# atsamdg21_rtc.net
KiCad netlist of a schematic drawn in EAGLE
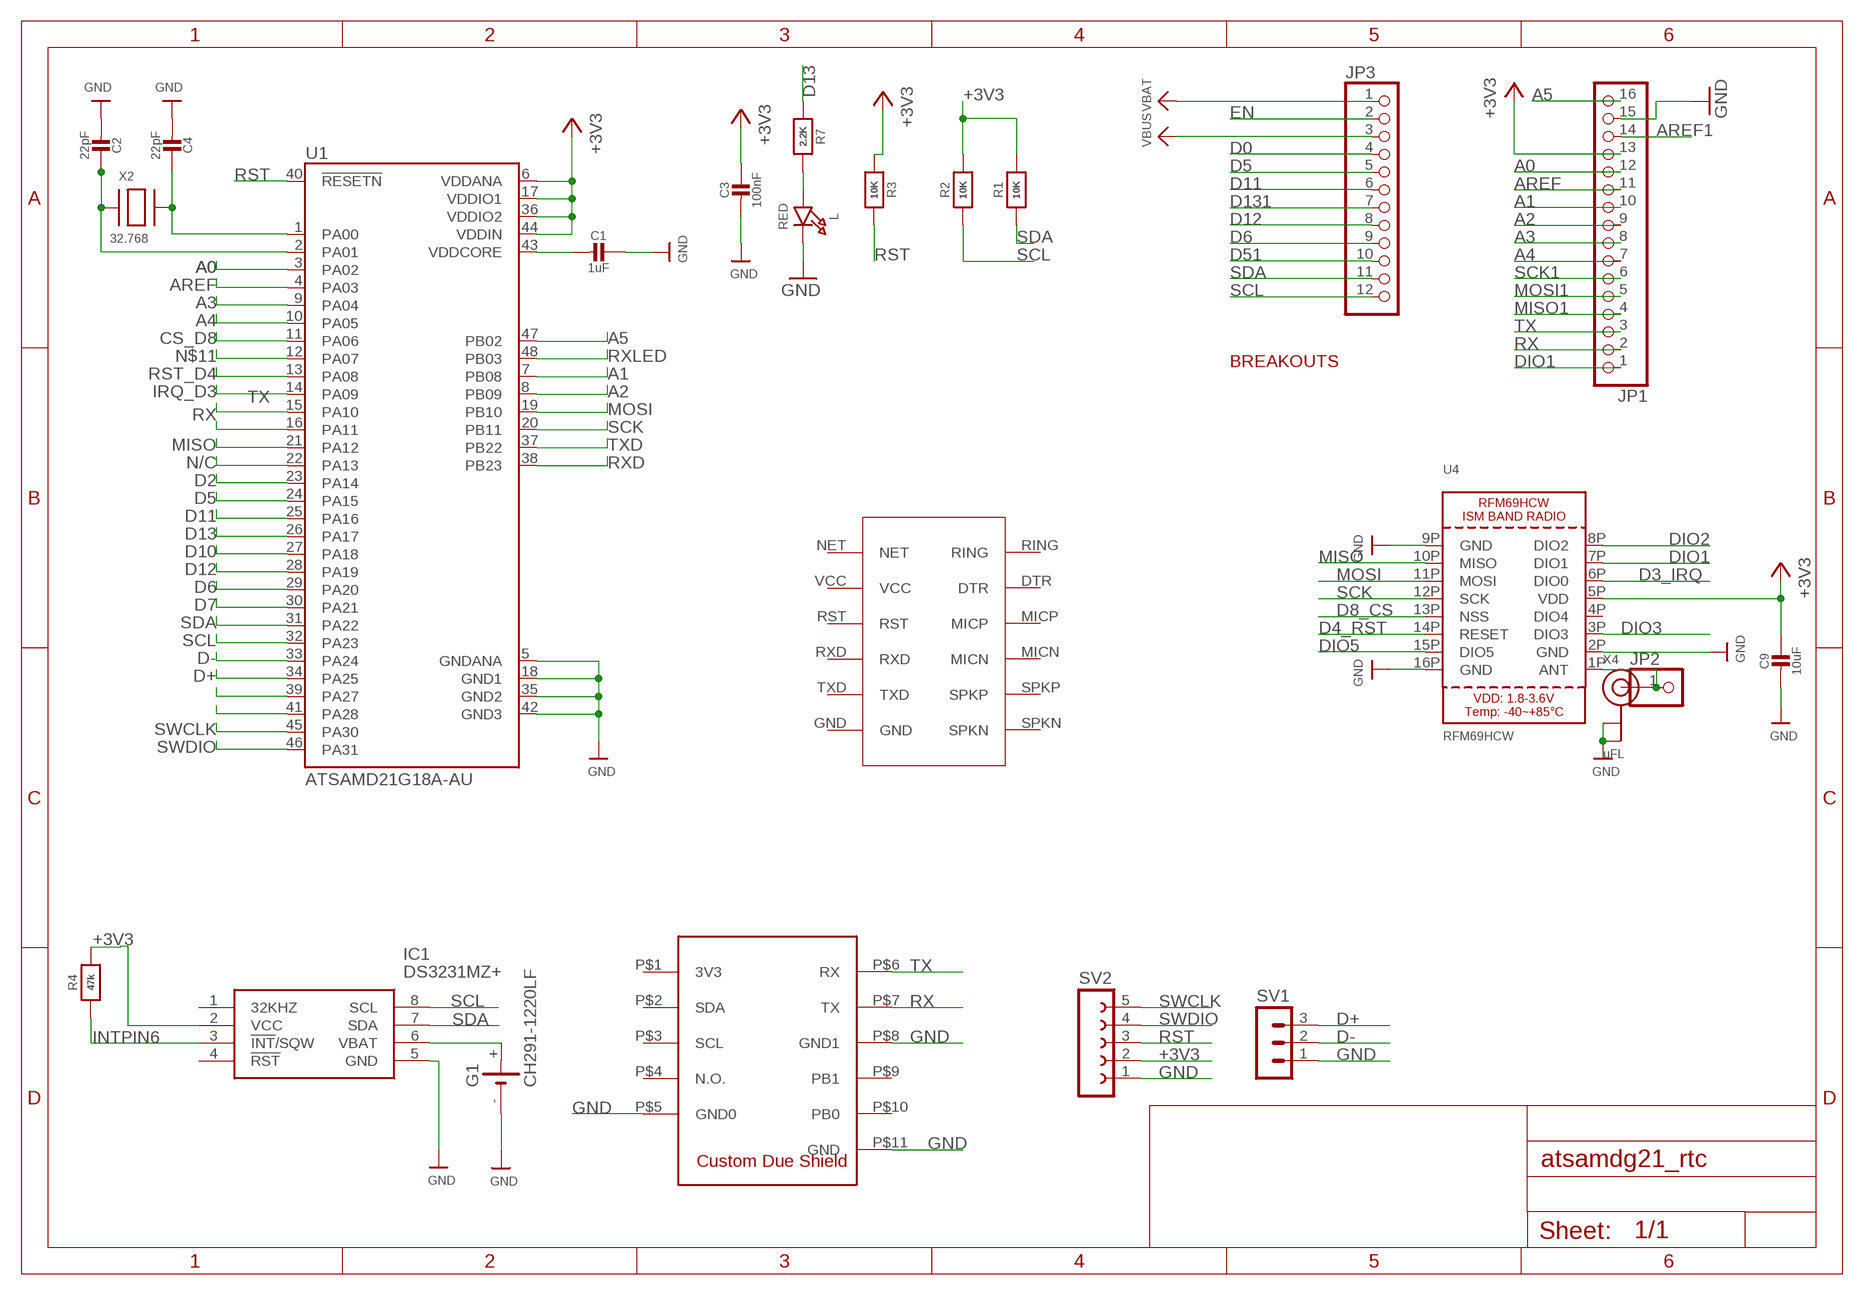
[diagram p0: schematic, sheet 1]

(export (version "E")
  (design (tool "Eeschema 10.0.6"))
  (components
    (comp (ref "C1")
      (value "1uF")
      (footprint "eagle-import:0603-NO")
      (libsource (lib "eagle-import") (part "CAP_CERAMIC0603_NO"))
    )
    (comp (ref "C2")
      (value "22pF")
      (footprint "eagle-import:0603-NO")
      (libsource (lib "eagle-import") (part "CAP_CERAMIC0603_NO"))
    )
    (comp (ref "C3")
      (value "100nF")
      (footprint "eagle-import:0603-NO")
      (libsource (lib "eagle-import") (part "CAP_CERAMIC0603_NO"))
    )
    (comp (ref "C4")
      (value "22pF")
      (footprint "eagle-import:0603-NO")
      (libsource (lib "eagle-import") (part "CAP_CERAMIC0603_NO"))
    )
    (comp (ref "C9")
      (value "10uF")
      (footprint "eagle-import:0805-NO")
      (libsource (lib "eagle-import") (part "CAP_CERAMIC0805-NOOUTLINE"))
    )
    (comp (ref "G1")
      (value "CH291-1220LF")
      (footprint "eagle-import:CH291-1220LF")
      (libsource (lib "eagle-import") (part "CH291-1220LF"))
    )
    (comp (ref "IC1")
      (value "DS3231MZ+")
      (footprint "eagle-import:SOIC127P600X175-8N")
      (fields (field (name "RS_PART_NUMBER") "1897249"))
      (libsource (lib "eagle-import") (part "DS3231MZ+"))
    )
    (comp (ref "JP1")
      (value "HEADER-1X16ROUND")
      (footprint "eagle-import:1X16_ROUND")
      (libsource (lib "eagle-import") (part "HEADER-1X16ROUND"))
    )
    (comp (ref "JP2")
      (value "HEADER-1X1ROUND")
      (footprint "eagle-import:1X01_ROUND")
      (libsource (lib "eagle-import") (part "HEADER-1X1ROUND"))
    )
    (comp (ref "JP3")
      (value "HEADER-1X12")
      (footprint "eagle-import:1X12_ROUND")
      (libsource (lib "eagle-import") (part "HEADER-1X12"))
    )
    (comp (ref "L")
      (value "RED")
      (footprint "eagle-import:CHIPLED_0805_NOOUTLINE")
      (libsource (lib "eagle-import") (part "LED0805_NOOUTLINE"))
    )
    (comp (ref "R1")
      (value "10K")
      (footprint "eagle-import:0603-NO")
      (libsource (lib "eagle-import") (part "RESISTOR_0603_NOOUT"))
    )
    (comp (ref "R2")
      (value "10K")
      (footprint "eagle-import:0603-NO")
      (libsource (lib "eagle-import") (part "RESISTOR_0603_NOOUT"))
    )
    (comp (ref "R3")
      (value "10K")
      (footprint "eagle-import:0603-NO")
      (libsource (lib "eagle-import") (part "RESISTOR_0603_NOOUT"))
    )
    (comp (ref "R4")
      (value "47k")
      (footprint "eagle-import:0603-NO")
      (libsource (lib "eagle-import") (part "RESISTOR_0603_NOOUT"))
    )
    (comp (ref "R7")
      (value "2.2K")
      (footprint "eagle-import:0603-NO")
      (libsource (lib "eagle-import") (part "RESISTOR_0603_NOOUT"))
    )
    (comp (ref "SV1")
      (value "MA03-1")
      (footprint "eagle-import:MA03-1")
      (libsource (lib "eagle-import") (part "MA03-1"))
    )
    (comp (ref "SV2")
      (value "FE05-1")
      (footprint "eagle-import:FE05-1")
      (libsource (lib "eagle-import") (part "FE05-1"))
    )
    (comp (ref "U$7")
      (value "SIM800L_MODULE")
      (footprint "eagle-import:SIM800L")
      (libsource (lib "eagle-import") (part "SIM800L_MODULE"))
    )
    (comp (ref "U$9")
      (value "DUE_PADS")
      (footprint "eagle-import:DUESHIELD")
      (libsource (lib "eagle-import") (part "DUE_PADS"))
    )
    (comp (ref "U1")
      (value "ATSAMD21G18A-AU")
      (footprint "eagle-import:QFP50P900X900X120-48N")
      (fields (field (name "MF") "Microchip"))
      (libsource (lib "eagle-import") (part "ATSAMD21G18A-AU"))
    )
    (comp (ref "U4")
      (value "RFM69HCW")
      (footprint "eagle-import:RFMHCW_SMT")
      (libsource (lib "eagle-import") (part "RFM69HCW_SMT"))
    )
    (comp (ref "X2")
      (value "32.768")
      (footprint "eagle-import:XTAL3215")
      (libsource (lib "eagle-import") (part "XTAL-3.2X1.5"))
    )
    (comp (ref "X4")
      (value "uFL")
      (footprint "eagle-import:U.FL")
      (libsource (lib "eagle-import") (part "ANTENNA_U.FL"))
    )
  )
  (nets
    (net (code "1") (name "+3V3") (class "Default")
      (node (ref "C3") (pin "1") (pinfunction "1_1") (pintype "passive"))
      (node (ref "C9") (pin "1") (pinfunction "1_1") (pintype "passive"))
      (node (ref "IC1") (pin "2") (pinfunction "VCC_2") (pintype "power_in"))
      (node (ref "JP1") (pin "13") (pinfunction "13_13") (pintype "passive"))
      (node (ref "R1") (pin "2") (pinfunction "2_2") (pintype "passive"))
      (node (ref "R2") (pin "2") (pinfunction "2_2") (pintype "passive"))
      (node (ref "R3") (pin "1") (pinfunction "1_1") (pintype "passive"))
      (node (ref "R4") (pin "2") (pinfunction "2_2") (pintype "passive"))
      (node (ref "SV2") (pin "2") (pinfunction "2_2") (pintype "passive"))
      (node (ref "U1") (pin "17") (pinfunction "VDDIO1_17") (pintype "power_in"))
      (node (ref "U1") (pin "36") (pinfunction "VDDIO2_36") (pintype "power_in"))
      (node (ref "U1") (pin "44") (pinfunction "VDDIN_44") (pintype "power_in"))
      (node (ref "U1") (pin "6") (pinfunction "VDDANA_6") (pintype "power_in"))
      (node (ref "U4") (pin "5P") (pinfunction "VDD_5P") (pintype "power_in"))
    )
    (net (code "2") (name "/A0") (class "Default")
      (node (ref "JP1") (pin "12") (pinfunction "12_12") (pintype "passive"))
      (node (ref "U1") (pin "3") (pinfunction "PA02_3") (pintype "bidirectional"))
    )
    (net (code "3") (name "/A1") (class "Default")
      (node (ref "JP1") (pin "10") (pinfunction "10_10") (pintype "passive"))
      (node (ref "U1") (pin "7") (pinfunction "PB08_7") (pintype "bidirectional"))
    )
    (net (code "4") (name "/A2") (class "Default")
      (node (ref "JP1") (pin "9") (pinfunction "9_9") (pintype "passive"))
      (node (ref "U1") (pin "8") (pinfunction "PB09_8") (pintype "bidirectional"))
    )
    (net (code "5") (name "/A3") (class "Default")
      (node (ref "JP1") (pin "8") (pinfunction "8_8") (pintype "passive"))
      (node (ref "U1") (pin "9") (pinfunction "PA04_9") (pintype "bidirectional"))
    )
    (net (code "6") (name "/A4") (class "Default")
      (node (ref "JP1") (pin "7") (pinfunction "7_7") (pintype "passive"))
      (node (ref "U1") (pin "10") (pinfunction "PA05_10") (pintype "bidirectional"))
    )
    (net (code "7") (name "/A5") (class "Default")
      (node (ref "JP1") (pin "16") (pinfunction "16_16") (pintype "passive"))
      (node (ref "U1") (pin "47") (pinfunction "PB02_47") (pintype "bidirectional"))
    )
    (net (code "8") (name "/AREF") (class "Default")
      (node (ref "JP1") (pin "11") (pinfunction "11_11") (pintype "passive"))
      (node (ref "U1") (pin "4") (pinfunction "PA03_4") (pintype "bidirectional"))
    )
    (net (code "9") (name "/AREF1") (class "Default")
      (node (ref "JP1") (pin "14") (pinfunction "14_14") (pintype "passive"))
    )
    (net (code "10") (name "/CS_D8") (class "Default")
      (node (ref "U1") (pin "11") (pinfunction "PA06_11") (pintype "bidirectional"))
    )
    (net (code "11") (name "/D+") (class "Default")
      (node (ref "SV1") (pin "3") (pinfunction "3_3") (pintype "passive"))
      (node (ref "U1") (pin "34") (pinfunction "PA25_34") (pintype "bidirectional"))
    )
    (net (code "12") (name "/D-") (class "Default")
      (node (ref "SV1") (pin "2") (pinfunction "2_2") (pintype "passive"))
      (node (ref "U1") (pin "33") (pinfunction "PA24_33") (pintype "bidirectional"))
    )
    (net (code "13") (name "/D0") (class "Default")
      (node (ref "JP3") (pin "4") (pinfunction "4_4") (pintype "passive"))
    )
    (net (code "14") (name "/D2") (class "Default")
      (node (ref "U1") (pin "23") (pinfunction "PA14_23") (pintype "bidirectional"))
    )
    (net (code "15") (name "/D3_IRQ") (class "Default")
      (node (ref "U4") (pin "6P") (pinfunction "DIO0_6P") (pintype "bidirectional"))
    )
    (net (code "16") (name "/D4_RST") (class "Default")
      (node (ref "U4") (pin "14P") (pinfunction "RESET_14P") (pintype "input"))
    )
    (net (code "17") (name "/D5") (class "Default")
      (node (ref "JP3") (pin "5") (pinfunction "5_5") (pintype "passive"))
      (node (ref "U1") (pin "24") (pinfunction "PA15_24") (pintype "bidirectional"))
    )
    (net (code "18") (name "/D6") (class "Default")
      (node (ref "JP3") (pin "9") (pinfunction "9_9") (pintype "passive"))
      (node (ref "U1") (pin "29") (pinfunction "PA20_29") (pintype "bidirectional"))
    )
    (net (code "19") (name "/D7") (class "Default")
      (node (ref "U1") (pin "30") (pinfunction "PA21_30") (pintype "bidirectional"))
    )
    (net (code "20") (name "/D8_CS") (class "Default")
      (node (ref "U4") (pin "13P") (pinfunction "NSS_13P") (pintype "input"))
    )
    (net (code "21") (name "/D10") (class "Default")
      (node (ref "U1") (pin "27") (pinfunction "PA18_27") (pintype "bidirectional"))
    )
    (net (code "22") (name "/D11") (class "Default")
      (node (ref "JP3") (pin "6") (pinfunction "6_6") (pintype "passive"))
      (node (ref "U1") (pin "25") (pinfunction "PA16_25") (pintype "bidirectional"))
    )
    (net (code "23") (name "/D12") (class "Default")
      (node (ref "JP3") (pin "8") (pinfunction "8_8") (pintype "passive"))
      (node (ref "U1") (pin "28") (pinfunction "PA19_28") (pintype "bidirectional"))
    )
    (net (code "24") (name "/D13") (class "Default")
      (node (ref "R7") (pin "1") (pinfunction "1_1") (pintype "passive"))
      (node (ref "U1") (pin "26") (pinfunction "PA17_26") (pintype "bidirectional"))
    )
    (net (code "25") (name "/D51") (class "Default")
      (node (ref "JP3") (pin "10") (pinfunction "10_10") (pintype "passive"))
    )
    (net (code "26") (name "/D131") (class "Default")
      (node (ref "JP3") (pin "7") (pinfunction "7_7") (pintype "passive"))
    )
    (net (code "27") (name "/DIO1") (class "Default")
      (node (ref "JP1") (pin "1") (pinfunction "1_1") (pintype "passive"))
      (node (ref "U4") (pin "7P") (pinfunction "DIO1_7P") (pintype "bidirectional"))
    )
    (net (code "28") (name "/DIO2") (class "Default")
      (node (ref "U4") (pin "8P") (pinfunction "DIO2_8P") (pintype "bidirectional"))
    )
    (net (code "29") (name "/DIO3") (class "Default")
      (node (ref "U4") (pin "3P") (pinfunction "DIO3_3P") (pintype "bidirectional"))
    )
    (net (code "30") (name "/DIO5") (class "Default")
      (node (ref "U4") (pin "15P") (pinfunction "DIO5_15P") (pintype "bidirectional"))
    )
    (net (code "31") (name "/EN") (class "Default")
      (node (ref "JP3") (pin "2") (pinfunction "2_2") (pintype "passive"))
    )
    (net (code "32") (name "/INTPIN6") (class "Default")
      (node (ref "IC1") (pin "3") (pinfunction "~{INT}/SQW_3") (pintype "input"))
      (node (ref "R4") (pin "1") (pinfunction "1_1") (pintype "passive"))
    )
    (net (code "33") (name "/IRQ_D3") (class "Default")
      (node (ref "U1") (pin "14") (pinfunction "PA09_14") (pintype "bidirectional"))
    )
    (net (code "34") (name "/MISO") (class "Default")
      (node (ref "U1") (pin "21") (pinfunction "PA12_21") (pintype "bidirectional"))
      (node (ref "U4") (pin "10P") (pinfunction "MISO_10P") (pintype "output"))
    )
    (net (code "35") (name "/MISO1") (class "Default")
      (node (ref "JP1") (pin "4") (pinfunction "4_4") (pintype "passive"))
    )
    (net (code "36") (name "/MOSI") (class "Default")
      (node (ref "U1") (pin "19") (pinfunction "PB10_19") (pintype "bidirectional"))
      (node (ref "U4") (pin "11P") (pinfunction "MOSI_11P") (pintype "input"))
    )
    (net (code "37") (name "/MOSI1") (class "Default")
      (node (ref "JP1") (pin "5") (pinfunction "5_5") (pintype "passive"))
    )
    (net (code "38") (name "/N$11") (class "Default")
      (node (ref "U1") (pin "12") (pinfunction "PA07_12") (pintype "bidirectional"))
    )
    (net (code "39") (name "/N{slash}C") (class "Default")
      (node (ref "U1") (pin "22") (pinfunction "PA13_22") (pintype "bidirectional"))
    )
    (net (code "40") (name "/RST") (class "Default")
      (node (ref "R3") (pin "2") (pinfunction "2_2") (pintype "passive"))
      (node (ref "SV2") (pin "3") (pinfunction "3_3") (pintype "passive"))
      (node (ref "U1") (pin "40") (pinfunction "~{RESETN}_40") (pintype "input"))
    )
    (net (code "41") (name "/RST_D4") (class "Default")
      (node (ref "U1") (pin "13") (pinfunction "PA08_13") (pintype "bidirectional"))
    )
    (net (code "42") (name "/RX") (class "Default")
      (node (ref "JP1") (pin "2") (pinfunction "2_2") (pintype "passive"))
      (node (ref "U$9") (pin "P$7") (pinfunction "TX_P$7") (pintype "bidirectional"))
      (node (ref "U1") (pin "16") (pinfunction "PA11_16") (pintype "bidirectional"))
    )
    (net (code "43") (name "/RXD") (class "Default")
      (node (ref "U1") (pin "38") (pinfunction "PB23_38") (pintype "bidirectional"))
    )
    (net (code "44") (name "/RXLED") (class "Default")
      (node (ref "U1") (pin "48") (pinfunction "PB03_48") (pintype "bidirectional"))
    )
    (net (code "45") (name "/SCK") (class "Default")
      (node (ref "U1") (pin "20") (pinfunction "PB11_20") (pintype "bidirectional"))
      (node (ref "U4") (pin "12P") (pinfunction "SCK_12P") (pintype "input"))
    )
    (net (code "46") (name "/SCK1") (class "Default")
      (node (ref "JP1") (pin "6") (pinfunction "6_6") (pintype "passive"))
    )
    (net (code "47") (name "/SCL") (class "Default")
      (node (ref "IC1") (pin "8") (pinfunction "SCL_8") (pintype "bidirectional"))
      (node (ref "JP3") (pin "12") (pinfunction "12_12") (pintype "passive"))
      (node (ref "R2") (pin "1") (pinfunction "1_1") (pintype "passive"))
      (node (ref "U1") (pin "32") (pinfunction "PA23_32") (pintype "bidirectional"))
    )
    (net (code "48") (name "/SDA") (class "Default")
      (node (ref "IC1") (pin "7") (pinfunction "SDA_7") (pintype "bidirectional"))
      (node (ref "JP3") (pin "11") (pinfunction "11_11") (pintype "passive"))
      (node (ref "R1") (pin "1") (pinfunction "1_1") (pintype "passive"))
      (node (ref "U1") (pin "31") (pinfunction "PA22_31") (pintype "bidirectional"))
    )
    (net (code "49") (name "/SWCLK") (class "Default")
      (node (ref "SV2") (pin "5") (pinfunction "5_5") (pintype "passive"))
      (node (ref "U1") (pin "45") (pinfunction "PA30_45") (pintype "bidirectional"))
    )
    (net (code "50") (name "/SWDIO") (class "Default")
      (node (ref "SV2") (pin "4") (pinfunction "4_4") (pintype "passive"))
      (node (ref "U1") (pin "46") (pinfunction "PA31_46") (pintype "bidirectional"))
    )
    (net (code "51") (name "/TX") (class "Default")
      (node (ref "JP1") (pin "3") (pinfunction "3_3") (pintype "passive"))
      (node (ref "U$9") (pin "P$6") (pinfunction "RX_P$6") (pintype "bidirectional"))
      (node (ref "U1") (pin "15") (pinfunction "PA10_15") (pintype "bidirectional"))
    )
    (net (code "52") (name "/TXD") (class "Default")
      (node (ref "U1") (pin "37") (pinfunction "PB22_37") (pintype "bidirectional"))
    )
    (net (code "53") (name "GND") (class "Default")
      (node (ref "C1") (pin "1") (pinfunction "1_1") (pintype "passive"))
      (node (ref "C2") (pin "2") (pinfunction "2_2") (pintype "passive"))
      (node (ref "C3") (pin "2") (pinfunction "2_2") (pintype "passive"))
      (node (ref "C4") (pin "2") (pinfunction "2_2") (pintype "passive"))
      (node (ref "C9") (pin "2") (pinfunction "2_2") (pintype "passive"))
      (node (ref "G1") (pin "-") (pinfunction "-_-") (pintype "passive"))
      (node (ref "IC1") (pin "5") (pinfunction "GND_5") (pintype "power_in"))
      (node (ref "JP1") (pin "15") (pinfunction "15_15") (pintype "passive"))
      (node (ref "L") (pin "C") (pinfunction "C_C") (pintype "passive"))
      (node (ref "SV1") (pin "1") (pinfunction "1_1") (pintype "passive"))
      (node (ref "SV2") (pin "1") (pinfunction "1_1") (pintype "passive"))
      (node (ref "U$9") (pin "P$11") (pinfunction "GND_P$11") (pintype "bidirectional"))
      (node (ref "U$9") (pin "P$5") (pinfunction "GND0_P$5") (pintype "bidirectional"))
      (node (ref "U$9") (pin "P$8") (pinfunction "GND1_P$8") (pintype "bidirectional"))
      (node (ref "U1") (pin "18") (pinfunction "GND1_18") (pintype "power_in"))
      (node (ref "U1") (pin "35") (pinfunction "GND2_35") (pintype "power_in"))
      (node (ref "U1") (pin "42") (pinfunction "GND3_42") (pintype "power_in"))
      (node (ref "U1") (pin "5") (pinfunction "GNDANA_5") (pintype "power_in"))
      (node (ref "U4") (pin "16P") (pinfunction "GND_16P") (pintype "power_in"))
      (node (ref "U4") (pin "2P") (pinfunction "GND_2P") (pintype "power_in"))
      (node (ref "U4") (pin "9P") (pinfunction "GND_9P") (pintype "power_in"))
      (node (ref "X4") (pin "1") (pinfunction "GND_1") (pintype "passive"))
      (node (ref "X4") (pin "2") (pinfunction "GND_2") (pintype "passive"))
    )
    (net (code "54") (name "Net-(IC1-VBAT)") (class "Default")
      (node (ref "G1") (pin "+") (pinfunction "+_+") (pintype "passive"))
      (node (ref "IC1") (pin "6") (pinfunction "VBAT_6") (pintype "bidirectional"))
    )
    (net (code "55") (name "Net-(L-PadA)") (class "Default")
      (node (ref "L") (pin "A") (pinfunction "A_A") (pintype "passive"))
      (node (ref "R7") (pin "2") (pinfunction "2_2") (pintype "passive"))
    )
    (net (code "56") (name "Net-(U1-PA00)") (class "Default")
      (node (ref "C4") (pin "1") (pinfunction "1_1") (pintype "passive"))
      (node (ref "U1") (pin "1") (pinfunction "PA00_1") (pintype "bidirectional"))
      (node (ref "X2") (pin "P$2") (pinfunction "P$2_P$2") (pintype "bidirectional"))
    )
    (net (code "57") (name "Net-(U1-PA01)") (class "Default")
      (node (ref "C2") (pin "1") (pinfunction "1_1") (pintype "passive"))
      (node (ref "U1") (pin "2") (pinfunction "PA01_2") (pintype "bidirectional"))
      (node (ref "X2") (pin "P$1") (pinfunction "P$1_P$1") (pintype "bidirectional"))
    )
    (net (code "58") (name "Net-(U1-VDDCORE)") (class "Default")
      (node (ref "C1") (pin "2") (pinfunction "2_2") (pintype "passive"))
      (node (ref "U1") (pin "43") (pinfunction "VDDCORE_43") (pintype "power_in"))
    )
    (net (code "59") (name "Net-(U4-ANT)") (class "Default")
      (node (ref "JP2") (pin "1") (pinfunction "1_1") (pintype "passive"))
      (node (ref "U4") (pin "1P") (pinfunction "ANT_1P") (pintype "bidirectional"))
      (node (ref "X4") (pin "3") (pinfunction "SIGNAL_3") (pintype "passive"))
    )
    (net (code "60") (name "VBAT") (class "Default")
      (node (ref "JP3") (pin "1") (pinfunction "1_1") (pintype "passive"))
    )
    (net (code "61") (name "VBUS") (class "Default")
      (node (ref "JP3") (pin "3") (pinfunction "3_3") (pintype "passive"))
    )
    (net (code "62") (name "unconnected-(IC1-32KHZ-Pad1)") (class "Default")
      (node (ref "IC1") (pin "1") (pinfunction "32KHZ_1") (pintype "bidirectional"))
    )
    (net (code "63") (name "unconnected-(IC1-~{RST}-Pad4)") (class "Default")
      (node (ref "IC1") (pin "4") (pinfunction "~{RST}_4") (pintype "input"))
    )
    (net (code "64") (name "unconnected-(U$7-PadDTR)") (class "Default")
      (node (ref "U$7") (pin "DTR") (pinfunction "DTR_DTR") (pintype "bidirectional"))
    )
    (net (code "65") (name "unconnected-(U$7-PadGND)") (class "Default")
      (node (ref "U$7") (pin "GND") (pinfunction "GND_GND") (pintype "bidirectional"))
    )
    (net (code "66") (name "unconnected-(U$7-PadMICN)") (class "Default")
      (node (ref "U$7") (pin "MICN") (pinfunction "MICN_MICN") (pintype "bidirectional"))
    )
    (net (code "67") (name "unconnected-(U$7-PadMICP)") (class "Default")
      (node (ref "U$7") (pin "MICP") (pinfunction "MICP_MICP") (pintype "bidirectional"))
    )
    (net (code "68") (name "unconnected-(U$7-PadNET)") (class "Default")
      (node (ref "U$7") (pin "NET") (pinfunction "NET_NET") (pintype "bidirectional"))
    )
    (net (code "69") (name "unconnected-(U$7-PadRING)") (class "Default")
      (node (ref "U$7") (pin "RING") (pinfunction "RING_RING") (pintype "bidirectional"))
    )
    (net (code "70") (name "unconnected-(U$7-PadRST)") (class "Default")
      (node (ref "U$7") (pin "RST") (pinfunction "RST_RST") (pintype "bidirectional"))
    )
    (net (code "71") (name "unconnected-(U$7-PadRXD)") (class "Default")
      (node (ref "U$7") (pin "RXD") (pinfunction "RXD_RXD") (pintype "bidirectional"))
    )
    (net (code "72") (name "unconnected-(U$7-PadSPKN)") (class "Default")
      (node (ref "U$7") (pin "SPKN") (pinfunction "SPKN_SPKN") (pintype "bidirectional"))
    )
    (net (code "73") (name "unconnected-(U$7-PadSPKP)") (class "Default")
      (node (ref "U$7") (pin "SPKP") (pinfunction "SPKP_SPKP") (pintype "bidirectional"))
    )
    (net (code "74") (name "unconnected-(U$7-PadTXD)") (class "Default")
      (node (ref "U$7") (pin "TXD") (pinfunction "TXD_TXD") (pintype "bidirectional"))
    )
    (net (code "75") (name "unconnected-(U$7-PadVCC)") (class "Default")
      (node (ref "U$7") (pin "VCC") (pinfunction "VCC_VCC") (pintype "bidirectional"))
    )
    (net (code "76") (name "unconnected-(U$9-3V3-PadP$1)") (class "Default")
      (node (ref "U$9") (pin "P$1") (pinfunction "3V3_P$1") (pintype "bidirectional"))
    )
    (net (code "77") (name "unconnected-(U$9-N.O.-PadP$4)") (class "Default")
      (node (ref "U$9") (pin "P$4") (pinfunction "N.O._P$4") (pintype "bidirectional"))
    )
    (net (code "78") (name "unconnected-(U$9-PB0-PadP$10)") (class "Default")
      (node (ref "U$9") (pin "P$10") (pinfunction "PB0_P$10") (pintype "bidirectional"))
    )
    (net (code "79") (name "unconnected-(U$9-PB1-PadP$9)") (class "Default")
      (node (ref "U$9") (pin "P$9") (pinfunction "PB1_P$9") (pintype "bidirectional"))
    )
    (net (code "80") (name "unconnected-(U$9-SCL-PadP$3)") (class "Default")
      (node (ref "U$9") (pin "P$3") (pinfunction "SCL_P$3") (pintype "bidirectional"))
    )
    (net (code "81") (name "unconnected-(U$9-SDA-PadP$2)") (class "Default")
      (node (ref "U$9") (pin "P$2") (pinfunction "SDA_P$2") (pintype "bidirectional"))
    )
    (net (code "82") (name "unconnected-(U1-PA27-Pad39)") (class "Default")
      (node (ref "U1") (pin "39") (pinfunction "PA27_39") (pintype "bidirectional"))
    )
    (net (code "83") (name "unconnected-(U1-PA28-Pad41)") (class "Default")
      (node (ref "U1") (pin "41") (pinfunction "PA28_41") (pintype "bidirectional"))
    )
    (net (code "84") (name "unconnected-(U4-DIO4-Pad4P)") (class "Default")
      (node (ref "U4") (pin "4P") (pinfunction "DIO4_4P") (pintype "bidirectional"))
    )
  )
)
